# Power_Regulation.net
KiCad netlist of a schematic drawn in Altium Designer
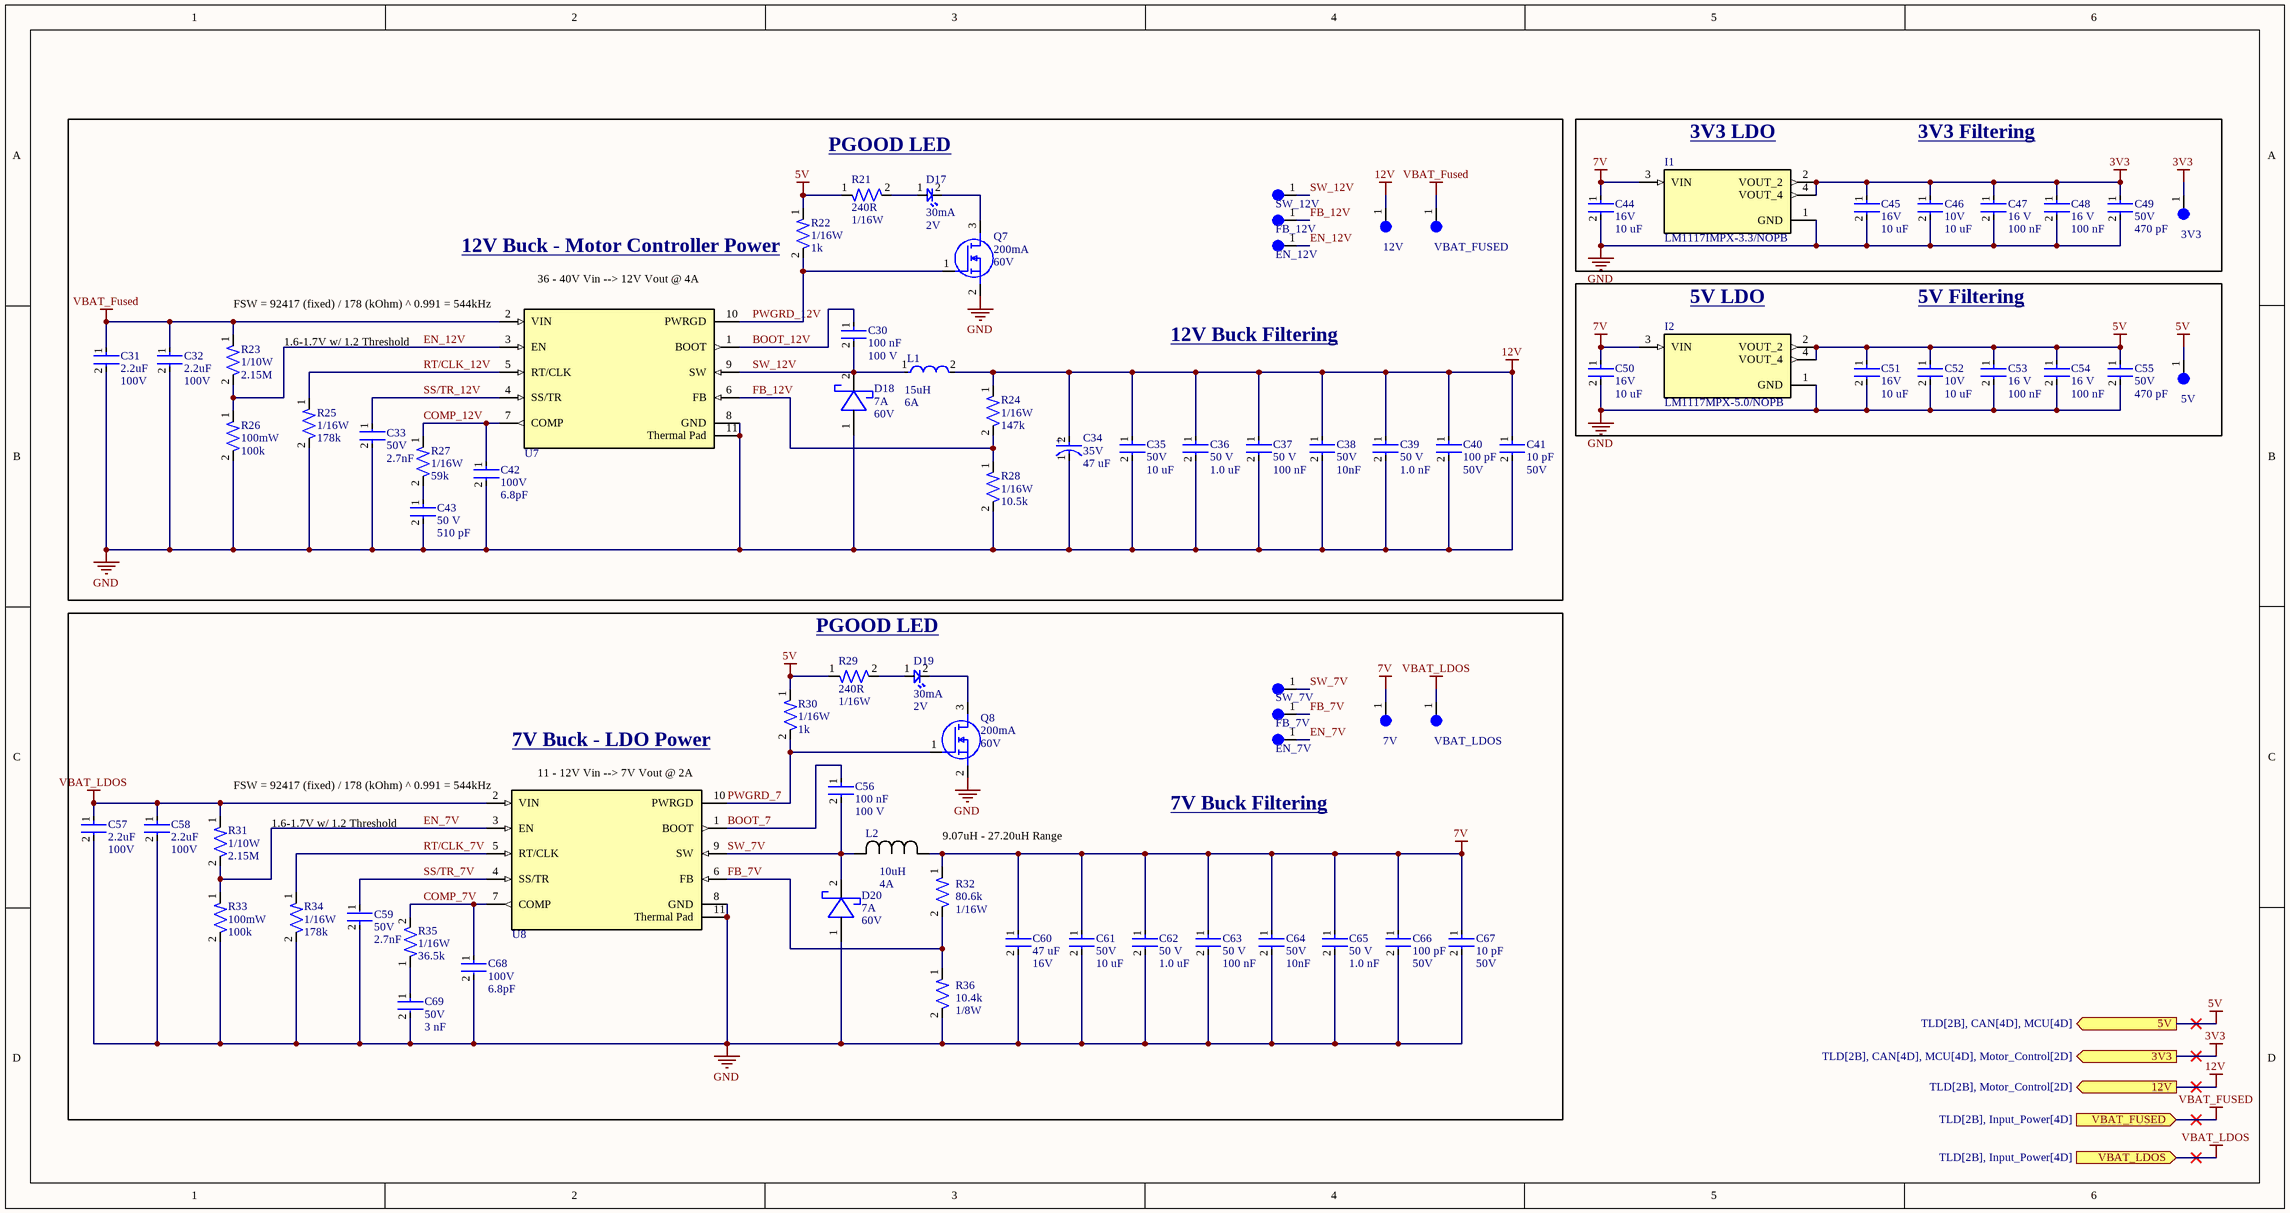
[diagram p0: Power_Regulation.SchDoc]

(export (version "E")
  (design (tool "Eeschema 10.0.6"))
  (components
    (comp (ref "3V3")
      (value "5003")
      (footprint "TEST-POINT-0001")
      (description "Oranange PC Test Point, Miniature Phoisphor Bronze Silver Plating Through Hole Mounting Type")
      (libsource (lib "*") (part "TEST-POINT-0001"))
    )
    (comp (ref "5V")
      (value "5003")
      (footprint "TEST-POINT-0001")
      (description "Oranange PC Test Point, Miniature Phoisphor Bronze Silver Plating Through Hole Mounting Type")
      (libsource (lib "*") (part "TEST-POINT-0001"))
    )
    (comp (ref "7V")
      (value "5003")
      (footprint "TEST-POINT-0001")
      (description "Oranange PC Test Point, Miniature Phoisphor Bronze Silver Plating Through Hole Mounting Type")
      (libsource (lib "*") (part "TEST-POINT-0001"))
    )
    (comp (ref "12V")
      (value "5003")
      (footprint "TEST-POINT-0001")
      (description "Oranange PC Test Point, Miniature Phoisphor Bronze Silver Plating Through Hole Mounting Type")
      (libsource (lib "*") (part "TEST-POINT-0001"))
    )
    (comp (ref "C30")
      (value "CC0603KRX7R0BB104")
      (footprint "CAP-0603")
      (description "CAP CER 0.1UF 100V X7R 0603")
      (fields (field (name "CAPACITANCE") "100 nF") (field (name "VOLTAGE") "100 V"))
      (libsource (lib "JLC_25") (part "CAP-100N-0001"))
    )
    (comp (ref "C31")
      (value "CC1206KKX7R0BB225")
      (footprint "CAP-1206")
      (description "CAP CER 2.2UF 100V X7R 1206")
      (fields (field (name "CAPACITANCE") "2.2uF") (field (name "VOLTAGE") "100V"))
      (libsource (lib "JLC_25") (part "CAP-2.2U-0001"))
    )
    (comp (ref "C32")
      (value "CC1206KKX7R0BB225")
      (footprint "CAP-1206")
      (description "CAP CER 2.2UF 100V X7R 1206")
      (fields (field (name "CAPACITANCE") "2.2uF") (field (name "VOLTAGE") "100V"))
      (libsource (lib "JLC_25") (part "CAP-2.2U-0001"))
    )
    (comp (ref "C33")
      (value "GRM2165C1H272JA01D")
      (footprint "CAP-0805")
      (description "CAP CER 2700PF 50V C0G/NP0 0805")
      (fields (field (name "VOLTAGE") "50V") (field (name "CAPACITANCE") "2.7nF"))
      (libsource (lib "JLC_25") (part "CAP-2.7N-0001"))
    )
    (comp (ref "C34")
      (value "EEH-ZC1V470P")
      (footprint "CAP-Radial-SMD")
      (description "CAP ALUM HYBRID 47UF 20% 35V SMD")
      (fields (field (name "VOLTAGE") "35V") (field (name "CAPACITANCE") "47 uF"))
      (libsource (lib "JLC_25") (part "CAP-47U-0002"))
    )
    (comp (ref "C35")
      (value "CL32B106KBJNNNE")
      (footprint "CAP-1210")
      (description "CAP CER 10UF 50V X7R 1210")
      (fields (field (name "VOLTAGE") "50V") (field (name "CAPACITANCE") "10 uF"))
      (libsource (lib "JLC_25") (part "CAP-10U-0002"))
    )
    (comp (ref "C36")
      (value "CC0805KKX7R9BB105")
      (footprint "CAP-0805")
      (description "CAP CER 1UF 50V X7R 0805")
      (fields (field (name "VOLTAGE") "50 V") (field (name "CAPACITANCE") "1.0 uF"))
      (libsource (lib "JLC_25") (part "CAP-1U-0001"))
    )
    (comp (ref "C37")
      (value "CC0805KRX7R9BB104")
      (footprint "CAP-0805")
      (description "CAP CER 0.1UF 50V X7R 0805")
      (fields (field (name "VOLTAGE RATING") "50 V") (field (name "CAPACITANCE") "100 nF"))
      (libsource (lib "JLC_25") (part "CAP-0.1U-0002"))
    )
    (comp (ref "C38")
      (value "GRM2195C1H103JA01D")
      (footprint "CAP-0805")
      (description "CAP CER 10000PF 50V C0G/NP0 0805")
      (fields (field (name "VOLTAGE") "50V") (field (name "CAPACITANCE") "10nF"))
      (libsource (lib "JLC_25") (part "CAP-10N-0001"))
    )
    (comp (ref "C39")
      (value "CC0402KRX7R9BB102")
      (footprint "CAP-0402")
      (description "CAP CER 1000PF 50V X7R 0402")
      (fields (field (name "VOLTAGE") "50 V") (field (name "CAPACITANCE") "1.0 nF"))
      (libsource (lib "JLC_25") (part "CAP-1N-0001"))
    )
    (comp (ref "C40")
      (value "CC0402JRNPO9BN101")
      (footprint "CAP-0402")
      (description "CAP CER 100PF 50V C0G/NPO 0402")
      (fields (field (name "CAPACITANCE") "100 pF") (field (name "VOLTAGE") "50V"))
      (libsource (lib "JLC_25") (part "CAP-100P-0001"))
    )
    (comp (ref "C41")
      (value "CC0402JRNPO9BN100")
      (footprint "CAP-0402")
      (description "CAP CER 10PF 50V C0G/NPO 0402")
      (fields (field (name "CAPACITANCE") "10 pF") (field (name "VOLTAGE") "50V"))
      (libsource (lib "JLC_25") (part "CAP-10P-0001"))
    )
    (comp (ref "C42")
      (value "CC0603CRNPO0BN6R8")
      (footprint "CAP-0603")
      (description "CAP CER 6.8PF 100V C0G/NPO 0603")
      (fields (field (name "VOLTAGE") "100V") (field (name "CAPACITANCE") "6.8pF"))
      (libsource (lib "JLC_25") (part "CAP-6.8P-0001"))
    )
    (comp (ref "C43")
      (value "0402N511J500CT")
      (footprint "CAP-0402")
      (description "CAP CER 510PF 50V C0G/NP0 0402")
      (fields (field (name "VOLTAGE") "50 V") (field (name "CAPACITANCE") "510 pF"))
      (libsource (lib "JLC_25") (part "CAP-510P-0001"))
    )
    (comp (ref "C44")
      (value "293D106X9016A2TE3")
      (footprint "CAP-1206")
      (description "CAP TANT 10UF 10% 16V 1206")
      (fields (field (name "VOLTAGE") "16V") (field (name "CAPACITANCE") "10 uF"))
      (libsource (lib "JLC_25") (part "CAP-10U-0004"))
    )
    (comp (ref "C45")
      (value "293D106X9016A2TE3")
      (footprint "CAP-1206")
      (description "CAP TANT 10UF 10% 16V 1206")
      (fields (field (name "VOLTAGE") "16V") (field (name "CAPACITANCE") "10 uF"))
      (libsource (lib "JLC_25") (part "CAP-10U-0004"))
    )
    (comp (ref "C46")
      (value "CC0603KRX5R6BB106")
      (footprint "CAP-0603")
      (description "CAP CER 10UF 10V X5R 0603")
      (fields (field (name "VOLTAGE") "10V") (field (name "CAPACITANCE") "10 uF"))
      (libsource (lib "JLC_25") (part "CAP-10U-0001"))
    )
    (comp (ref "C47")
      (value "CC0402KRX7R7BB104")
      (footprint "CAP-0402")
      (description "CAP CER 0.1UF 16V X7R 0402")
      (fields (field (name "VOLTAGE RATING") "16 V") (field (name "CAPACITANCE") "100 nF"))
      (libsource (lib "JLC_25") (part "CAP-0.1U-0001"))
    )
    (comp (ref "C48")
      (value "CC0402KRX7R7BB104")
      (footprint "CAP-0402")
      (description "CAP CER 0.1UF 16V X7R 0402")
      (fields (field (name "VOLTAGE RATING") "16 V") (field (name "CAPACITANCE") "100 nF"))
      (libsource (lib "JLC_25") (part "CAP-0.1U-0001"))
    )
    (comp (ref "C49")
      (value "CC0805JRNPO9BN471")
      (footprint "CAP-0805")
      (description "CAP CER 470PF 50V C0G/NPO 0805")
      (fields (field (name "VOLTAGE") "50V") (field (name "CAPACITANCE") "470 pF"))
      (libsource (lib "JLC_25") (part "CAP-470P-0001"))
    )
    (comp (ref "C50")
      (value "293D106X9016A2TE3")
      (footprint "CAP-1206")
      (description "CAP TANT 10UF 10% 16V 1206")
      (fields (field (name "VOLTAGE") "16V") (field (name "CAPACITANCE") "10 uF"))
      (libsource (lib "JLC_25") (part "CAP-10U-0004"))
    )
    (comp (ref "C51")
      (value "293D106X9016A2TE3")
      (footprint "CAP-1206")
      (description "CAP TANT 10UF 10% 16V 1206")
      (fields (field (name "VOLTAGE") "16V") (field (name "CAPACITANCE") "10 uF"))
      (libsource (lib "JLC_25") (part "CAP-10U-0004"))
    )
    (comp (ref "C52")
      (value "CC0603KRX5R6BB106")
      (footprint "CAP-0603")
      (description "CAP CER 10UF 10V X5R 0603")
      (fields (field (name "VOLTAGE") "10V") (field (name "CAPACITANCE") "10 uF"))
      (libsource (lib "JLC_25") (part "CAP-10U-0001"))
    )
    (comp (ref "C53")
      (value "CC0402KRX7R7BB104")
      (footprint "CAP-0402")
      (description "CAP CER 0.1UF 16V X7R 0402")
      (fields (field (name "VOLTAGE RATING") "16 V") (field (name "CAPACITANCE") "100 nF"))
      (libsource (lib "JLC_25") (part "CAP-0.1U-0001"))
    )
    (comp (ref "C54")
      (value "CC0402KRX7R7BB104")
      (footprint "CAP-0402")
      (description "CAP CER 0.1UF 16V X7R 0402")
      (fields (field (name "VOLTAGE RATING") "16 V") (field (name "CAPACITANCE") "100 nF"))
      (libsource (lib "JLC_25") (part "CAP-0.1U-0001"))
    )
    (comp (ref "C55")
      (value "CC0805JRNPO9BN471")
      (footprint "CAP-0805")
      (description "CAP CER 470PF 50V C0G/NPO 0805")
      (fields (field (name "VOLTAGE") "50V") (field (name "CAPACITANCE") "470 pF"))
      (libsource (lib "JLC_25") (part "CAP-470P-0001"))
    )
    (comp (ref "C56")
      (value "CC0603KRX7R0BB104")
      (footprint "CAP-0603")
      (description "CAP CER 0.1UF 100V X7R 0603")
      (fields (field (name "CAPACITANCE") "100 nF") (field (name "VOLTAGE") "100 V"))
      (libsource (lib "JLC_25") (part "CAP-100N-0001"))
    )
    (comp (ref "C57")
      (value "CC1206KKX7R0BB225")
      (footprint "CAP-1206")
      (description "CAP CER 2.2UF 100V X7R 1206")
      (fields (field (name "CAPACITANCE") "2.2uF") (field (name "VOLTAGE") "100V"))
      (libsource (lib "JLC_25") (part "CAP-2.2U-0001"))
    )
    (comp (ref "C58")
      (value "CC1206KKX7R0BB225")
      (footprint "CAP-1206")
      (description "CAP CER 2.2UF 100V X7R 1206")
      (fields (field (name "CAPACITANCE") "2.2uF") (field (name "VOLTAGE") "100V"))
      (libsource (lib "JLC_25") (part "CAP-2.2U-0001"))
    )
    (comp (ref "C59")
      (value "GRM2165C1H272JA01D")
      (footprint "CAP-0805")
      (description "CAP CER 2700PF 50V C0G/NP0 0805")
      (fields (field (name "VOLTAGE") "50V") (field (name "CAPACITANCE") "2.7nF"))
      (libsource (lib "JLC_25") (part "CAP-2.7N-0001"))
    )
    (comp (ref "C60")
      (value "C3225X7R1N106K250AC")
      (footprint "CAP-1210")
      (description "CAP CER 47UF 16V X5R 1210")
      (fields (field (name "CAPACITANCE") "47 uF") (field (name "VOLTAGE") "16V"))
      (libsource (lib "JLC_25") (part "CAP-47U-0003"))
    )
    (comp (ref "C61")
      (value "CL32B106KBJNNNE")
      (footprint "CAP-1210")
      (description "CAP CER 10UF 50V X7R 1210")
      (fields (field (name "VOLTAGE") "50V") (field (name "CAPACITANCE") "10 uF"))
      (libsource (lib "JLC_25") (part "CAP-10U-0002"))
    )
    (comp (ref "C62")
      (value "CC0805KKX7R9BB105")
      (footprint "CAP-0805")
      (description "CAP CER 1UF 50V X7R 0805")
      (fields (field (name "VOLTAGE") "50 V") (field (name "CAPACITANCE") "1.0 uF"))
      (libsource (lib "JLC_25") (part "CAP-1U-0001"))
    )
    (comp (ref "C63")
      (value "CC0805KRX7R9BB104")
      (footprint "CAP-0805")
      (description "CAP CER 0.1UF 50V X7R 0805")
      (fields (field (name "VOLTAGE RATING") "50 V") (field (name "CAPACITANCE") "100 nF"))
      (libsource (lib "JLC_25") (part "CAP-0.1U-0002"))
    )
    (comp (ref "C64")
      (value "GRM2195C1H103JA01D")
      (footprint "CAP-0805")
      (description "CAP CER 10000PF 50V C0G/NP0 0805")
      (fields (field (name "VOLTAGE") "50V") (field (name "CAPACITANCE") "10nF"))
      (libsource (lib "JLC_25") (part "CAP-10N-0001"))
    )
    (comp (ref "C65")
      (value "CC0402KRX7R9BB102")
      (footprint "CAP-0402")
      (description "CAP CER 1000PF 50V X7R 0402")
      (fields (field (name "VOLTAGE") "50 V") (field (name "CAPACITANCE") "1.0 nF"))
      (libsource (lib "JLC_25") (part "CAP-1N-0001"))
    )
    (comp (ref "C66")
      (value "CC0402JRNPO9BN101")
      (footprint "CAP-0402")
      (description "CAP CER 100PF 50V C0G/NPO 0402")
      (fields (field (name "CAPACITANCE") "100 pF") (field (name "VOLTAGE") "50V"))
      (libsource (lib "JLC_25") (part "CAP-100P-0001"))
    )
    (comp (ref "C67")
      (value "CC0402JRNPO9BN100")
      (footprint "CAP-0402")
      (description "CAP CER 10PF 50V C0G/NPO 0402")
      (fields (field (name "CAPACITANCE") "10 pF") (field (name "VOLTAGE") "50V"))
      (libsource (lib "JLC_25") (part "CAP-10P-0001"))
    )
    (comp (ref "C68")
      (value "CC0603CRNPO0BN6R8")
      (footprint "CAP-0603")
      (description "CAP CER 6.8PF 100V C0G/NPO 0603")
      (fields (field (name "VOLTAGE") "100V") (field (name "CAPACITANCE") "6.8pF"))
      (libsource (lib "JLC_25") (part "CAP-6.8P-0001"))
    )
    (comp (ref "C69")
      (value "GRM1885C1H302JA01D")
      (footprint "CAP-0603")
      (description "3000 pF ±5% 50V Ceramic Capacitor C0G, NP0 0603 (1608 Metric)")
      (fields (field (name "VOLTAGE") "50V") (field (name "CAPACITANCE") "3 nF"))
      (libsource (lib "JLC_25") (part "CAP-3N-0001"))
    )
    (comp (ref "D17")
      (value "BL-HKC36G-AV-TRB")
      (footprint "LED-0603")
      (description "LED YELLOW CLEAR 0603 SMD")
      (fields (field (name "FORWARD CURRENT") "30mA") (field (name "FORWARD VOLTAGE") "2V"))
      (libsource (lib "JLC_25") (part "LED-0001"))
    )
    (comp (ref "D18")
      (value "PDS760-13")
      (footprint "DO-POWERDI5")
      (description "DIODE SCHOTTKY 60V 7A POWERDI5")
      (fields (field (name "FORWARD CURRENT") "7A") (field (name "REVERSE VOLTAGE (DC)") "60V"))
      (libsource (lib "JLC_25") (part "DIO-SCHOTTKY-0001"))
    )
    (comp (ref "D19")
      (value "BL-HKC36G-AV-TRB")
      (footprint "LED-0603")
      (description "LED YELLOW CLEAR 0603 SMD")
      (fields (field (name "FORWARD CURRENT") "30mA") (field (name "FORWARD VOLTAGE") "2V"))
      (libsource (lib "JLC_25") (part "LED-0001"))
    )
    (comp (ref "D20")
      (value "PDS760-13")
      (footprint "DO-POWERDI5")
      (description "DIODE SCHOTTKY 60V 7A POWERDI5")
      (fields (field (name "FORWARD CURRENT") "7A") (field (name "REVERSE VOLTAGE (DC)") "60V"))
      (libsource (lib "JLC_25") (part "DIO-SCHOTTKY-0001"))
    )
    (comp (ref "EN_7V")
      (value "5003")
      (footprint "TEST-POINT-0001")
      (description "Oranange PC Test Point, Miniature Phoisphor Bronze Silver Plating Through Hole Mounting Type")
      (libsource (lib "*") (part "TEST-POINT-0001"))
    )
    (comp (ref "EN_12V")
      (value "5003")
      (footprint "TEST-POINT-0001")
      (description "Oranange PC Test Point, Miniature Phoisphor Bronze Silver Plating Through Hole Mounting Type")
      (libsource (lib "*") (part "TEST-POINT-0001"))
    )
    (comp (ref "FB_7V")
      (value "5003")
      (footprint "TEST-POINT-0001")
      (description "Oranange PC Test Point, Miniature Phoisphor Bronze Silver Plating Through Hole Mounting Type")
      (libsource (lib "*") (part "TEST-POINT-0001"))
    )
    (comp (ref "FB_12V")
      (value "5003")
      (footprint "TEST-POINT-0001")
      (description "Oranange PC Test Point, Miniature Phoisphor Bronze Silver Plating Through Hole Mounting Type")
      (libsource (lib "*") (part "TEST-POINT-0001"))
    )
    (comp (ref "I1")
      (value "LM1117IMPX-3.3/NOPB")
      (footprint "IC-SOT-223-4")
      (description "IC REG LIN 3.3V 800MA SOT223-4")
      (libsource (lib "JLC_25") (part "IC_LDO_3V3_0001"))
    )
    (comp (ref "I2")
      (value "LM1117MPX-5.0/NOPB")
      (footprint "IC-SOT-223-4")
      (description "IC REG LINEAR 5V 800MA SOT223-4")
      (libsource (lib "JLC_25") (part "IC_LDO_5V_0001"))
    )
    (comp (ref "L1")
      (value "CSAD1010-150M")
      (footprint "IND-15U-0002")
      (description "SMD MOLDING POWER CHOKE")
      (fields (field (name "INDUCTANCE") "15uH") (field (name "CURRENT RATING") "6A"))
      (libsource (lib "JLC_25") (part "IND-15U-0002-NoJLC"))
    )
    (comp (ref "L2")
      (value "IHLP2525CZER100M11")
      (footprint "IND_IHLP_2525_CZ_VIS")
      (description "IHLP-2525CZ-11 10 20% ER E3")
      (fields
        (field (name "CURRENT") "4A")
        (field (name "INDUCTANCE") "10uH")
        (field (name "COPYRIGHT") "Copyright (C) 2025 Ultra Librarian. All rights reserved.")
      )
      (libsource (lib "JLC_25") (part "IND-10U-0002"))
    )
    (comp (ref "Q7")
      (value "T2N7002AK,LM")
      (footprint "IC-SOT23-3")
      (description "MOSFET N-CH 60V 200MA SOT23")
      (fields (field (name "CONTINUOUS CURRENT") "200mA") (field (name "VOLTAGE") "60V"))
      (libsource (lib "JLC_25") (part "NMOS-200MA-0001"))
    )
    (comp (ref "Q8")
      (value "T2N7002AK,LM")
      (footprint "IC-SOT23-3")
      (description "MOSFET N-CH 60V 200MA SOT23")
      (fields (field (name "CONTINUOUS CURRENT") "200mA") (field (name "VOLTAGE") "60V"))
      (libsource (lib "JLC_25") (part "NMOS-200MA-0001"))
    )
    (comp (ref "R21")
      (value "RC0402FR-07240RL")
      (footprint "RES-0402")
      (description "240R 0.063W 1% 0402 (1005 Metric)  SMD")
      (fields
        (field (name "TOLERANCE") "1%")
        (field (name "RESISTANCE") "240R")
        (field (name "POWER") "1/16W")
      )
      (libsource (lib "JLC_25") (part "RES-240-0001"))
    )
    (comp (ref "R22")
      (value "RC0402FR-071KL")
      (footprint "RES-0402")
      (description "RES 1K OHM 1% 1/16W 0402")
      (fields (field (name "TOLERANCE") "1%") (field (name "POWER") "1/16W") (field (name "RESISTANCE") "1k"))
      (libsource (lib "JLC_25") (part "RES-1k-0001"))
    )
    (comp (ref "R23")
      (value "RC0603FR-072M15L")
      (footprint "RES-0603")
      (description "RES SMD 2.15M OHM 1% 1/10W 0603")
      (fields
        (field (name "TOLERANCE") "1%")
        (field (name "POWER") "1/10W")
        (field (name "RESISTANCE") "2.15M")
      )
      (libsource (lib "JLC_25") (part "RES-2.15M-0001"))
    )
    (comp (ref "R24")
      (value "RC0402FR-07147KL")
      (footprint "RES-0402")
      (description "RES 147K OHM 1% 1/16W 0402")
      (fields
        (field (name "TOLERANCE") "1%")
        (field (name "POWER") "1/16W")
        (field (name "RESISTANCE") "147k")
      )
      (libsource (lib "JLC_25") (part "RES-147k-0001"))
    )
    (comp (ref "R25")
      (value "RTT021783FTH")
      (footprint "RES-0402")
      (description "62.5mW Thick Film Resistors 50V ±100ppm/℃ ±1% 178kΩ 0402 Chip Resistor - Surface Mount ROHS")
      (fields
        (field (name "TOLERANCE") "1%")
        (field (name "POWER") "1/16W")
        (field (name "RESISTANCE") "178k")
      )
      (libsource (lib "JLC_25") (part "RES-178k-0001"))
    )
    (comp (ref "R26")
      (value "RC0603FR-07100KL")
      (footprint "RES-0603")
      (description "RES SMD 100K OHM 1% 1/10W 0603")
      (fields
        (field (name "TOLERANCE") "1%")
        (field (name "POWER") "100mW")
        (field (name "RESISTANCE") "100k")
      )
      (libsource (lib "JLC_25") (part "RES-100k-0001"))
    )
    (comp (ref "R27")
      (value "RC0402FR-0759KL")
      (footprint "RES-0402")
      (description "RES 59K OHM 1% 1/16W 0402")
      (fields
        (field (name "TOLERANCE") "1%")
        (field (name "POWER") "1/16W")
        (field (name "RESISTANCE") "59k")
      )
      (libsource (lib "JLC_25") (part "RES-59k-0001"))
    )
    (comp (ref "R28")
      (value "RC0402FR-0710K5L")
      (footprint "RES-0402")
      (description "RES 10.5K OHM 1% 1/16W 0402")
      (fields
        (field (name "TOLERANCE") "1%")
        (field (name "POWER") "1/16W")
        (field (name "RESISTANCE") "10.5k")
      )
      (libsource (lib "JLC_25") (part "RES-10.5k-0001"))
    )
    (comp (ref "R29")
      (value "RC0402FR-07240RL")
      (footprint "RES-0402")
      (description "240R 0.063W 1% 0402 (1005 Metric)  SMD")
      (fields
        (field (name "TOLERANCE") "1%")
        (field (name "RESISTANCE") "240R")
        (field (name "POWER") "1/16W")
      )
      (libsource (lib "JLC_25") (part "RES-240-0001"))
    )
    (comp (ref "R30")
      (value "RC0402FR-071KL")
      (footprint "RES-0402")
      (description "RES 1K OHM 1% 1/16W 0402")
      (fields (field (name "TOLERANCE") "1%") (field (name "POWER") "1/16W") (field (name "RESISTANCE") "1k"))
      (libsource (lib "JLC_25") (part "RES-1k-0001"))
    )
    (comp (ref "R31")
      (value "RC0603FR-072M15L")
      (footprint "RES-0603")
      (description "RES SMD 2.15M OHM 1% 1/10W 0603")
      (fields
        (field (name "TOLERANCE") "1%")
        (field (name "POWER") "1/10W")
        (field (name "RESISTANCE") "2.15M")
      )
      (libsource (lib "JLC_25") (part "RES-2.15M-0001"))
    )
    (comp (ref "R32")
      (value "RC0402FR-0780K6L")
      (footprint "RES-0402")
      (description "80.6 kOhms ±1% 0.063W, 1/16W Chip Resistor 0402 (1005 Metric) Moisture Resistant Thick Film")
      (fields
        (field (name "TOLERANCE") "1%")
        (field (name "RESISTANCE") "80.6k")
        (field (name "POWER") "1/16W")
      )
      (libsource (lib "JLC_25") (part "RES-80.6k-0001"))
    )
    (comp (ref "R33")
      (value "RC0603FR-07100KL")
      (footprint "RES-0603")
      (description "RES SMD 100K OHM 1% 1/10W 0603")
      (fields
        (field (name "TOLERANCE") "1%")
        (field (name "POWER") "100mW")
        (field (name "RESISTANCE") "100k")
      )
      (libsource (lib "JLC_25") (part "RES-100k-0001"))
    )
    (comp (ref "R34")
      (value "RTT021783FTH")
      (footprint "RES-0402")
      (description "62.5mW Thick Film Resistors 50V ±100ppm/℃ ±1% 178kΩ 0402 Chip Resistor - Surface Mount ROHS")
      (fields
        (field (name "TOLERANCE") "1%")
        (field (name "POWER") "1/16W")
        (field (name "RESISTANCE") "178k")
      )
      (libsource (lib "JLC_25") (part "RES-178k-0001"))
    )
    (comp (ref "R35")
      (value "RC0402FR-0736K5L")
      (footprint "RES-0402")
      (description "36.5 kOhms ±1% 0.063W, 1/16W Chip Resistor 0402 (1005 Metric) Moisture Resistant Thick Film")
      (fields (field (name "POWER") "1/16W") (field (name "RESISTANCE") "36.5k"))
      (libsource (lib "JLC_25") (part "RES-36.5k-0001"))
    )
    (comp (ref "R36")
      (value "RT0805BRD0710K4L")
      (footprint "RES-0805")
      (description "10.4 kOhms ±0.1% 0.125W, 1/8W Chip Resistor 0805 (2012 Metric) Thin Film")
      (fields
        (field (name "TOLERANCE") "1%")
        (field (name "POWER") "1/8W")
        (field (name "RESISTANCE") "10.4k")
      )
      (libsource (lib "JLC_25") (part "RES-10.4k-0001"))
    )
    (comp (ref "SW_7V")
      (value "5003")
      (footprint "TEST-POINT-0001")
      (description "Oranange PC Test Point, Miniature Phoisphor Bronze Silver Plating Through Hole Mounting Type")
      (libsource (lib "*") (part "TEST-POINT-0001"))
    )
    (comp (ref "SW_12V")
      (value "5003")
      (footprint "TEST-POINT-0001")
      (description "Oranange PC Test Point, Miniature Phoisphor Bronze Silver Plating Through Hole Mounting Type")
      (libsource (lib "*") (part "TEST-POINT-0001"))
    )
    (comp (ref "U7")
      (value "TPS54561DPRR")
      (footprint "IC-10WSON")
      (description "IC REG BUCK ADJ 5A 10WSON")
      (libsource (lib "JLC_25") (part "IC-BUCK-0001"))
    )
    (comp (ref "U8")
      (value "TPS54561DPRR")
      (footprint "IC-10WSON")
      (description "IC REG BUCK ADJ 5A 10WSON")
      (libsource (lib "JLC_25") (part "IC-BUCK-0001"))
    )
    (comp (ref "VBAT_FUSED")
      (value "5003")
      (footprint "TEST-POINT-0001")
      (description "Oranange PC Test Point, Miniature Phoisphor Bronze Silver Plating Through Hole Mounting Type")
      (libsource (lib "*") (part "TEST-POINT-0001"))
    )
    (comp (ref "VBAT_LDOS")
      (value "5003")
      (footprint "TEST-POINT-0001")
      (description "Oranange PC Test Point, Miniature Phoisphor Bronze Silver Plating Through Hole Mounting Type")
      (libsource (lib "*") (part "TEST-POINT-0001"))
    )
  )
  (nets
    (net (code "1") (name "/BOOT_7") (class "Default")
      (node (ref "C56") (pin "1") (pinfunction "1_1") (pintype "passive"))
      (node (ref "U8") (pin "1") (pinfunction "BOOT_1") (pintype "output"))
    )
    (net (code "2") (name "/BOOT_12V") (class "Default")
      (node (ref "C30") (pin "1") (pinfunction "1_1") (pintype "passive"))
      (node (ref "U7") (pin "1") (pinfunction "BOOT_1") (pintype "output"))
    )
    (net (code "3") (name "/COMP_7V") (class "Default")
      (node (ref "C68") (pin "1") (pinfunction "1_1") (pintype "passive"))
      (node (ref "R35") (pin "2") (pinfunction "2_2") (pintype "passive"))
      (node (ref "U8") (pin "7") (pinfunction "COMP_7") (pintype "output"))
    )
    (net (code "4") (name "/COMP_12V") (class "Default")
      (node (ref "C42") (pin "1") (pinfunction "1_1") (pintype "passive"))
      (node (ref "R27") (pin "1") (pinfunction "1_1") (pintype "passive"))
      (node (ref "U7") (pin "7") (pinfunction "COMP_7") (pintype "output"))
    )
    (net (code "5") (name "/EN_7V") (class "Default")
      (node (ref "EN_7V") (pin "1") (pinfunction "0_1") (pintype "passive"))
      (node (ref "R31") (pin "2") (pinfunction "2_2") (pintype "passive"))
      (node (ref "R33") (pin "1") (pinfunction "1_1") (pintype "passive"))
      (node (ref "U8") (pin "3") (pinfunction "EN_3") (pintype "input"))
    )
    (net (code "6") (name "/EN_12V") (class "Default")
      (node (ref "EN_12V") (pin "1") (pinfunction "0_1") (pintype "passive"))
      (node (ref "R23") (pin "2") (pinfunction "2_2") (pintype "passive"))
      (node (ref "R26") (pin "1") (pinfunction "1_1") (pintype "passive"))
      (node (ref "U7") (pin "3") (pinfunction "EN_3") (pintype "input"))
    )
    (net (code "7") (name "/FB_7V") (class "Default")
      (node (ref "FB_7V") (pin "1") (pinfunction "0_1") (pintype "passive"))
      (node (ref "R32") (pin "2") (pinfunction "2_2") (pintype "passive"))
      (node (ref "R36") (pin "1") (pinfunction "1_1") (pintype "passive"))
      (node (ref "U8") (pin "6") (pinfunction "FB_6") (pintype "input"))
    )
    (net (code "8") (name "/FB_12V") (class "Default")
      (node (ref "FB_12V") (pin "1") (pinfunction "0_1") (pintype "passive"))
      (node (ref "R24") (pin "2") (pinfunction "2_2") (pintype "passive"))
      (node (ref "R28") (pin "1") (pinfunction "1_1") (pintype "passive"))
      (node (ref "U7") (pin "6") (pinfunction "FB_6") (pintype "input"))
    )
    (net (code "9") (name "/PWGRD_7") (class "Default")
      (node (ref "Q8") (pin "1") (pinfunction "G_1") (pintype "passive"))
      (node (ref "R30") (pin "2") (pinfunction "2_2") (pintype "passive"))
      (node (ref "U8") (pin "10") (pinfunction "PWRGD_10") (pintype "open_collector"))
    )
    (net (code "10") (name "/PWGRD_12V") (class "Default")
      (node (ref "Q7") (pin "1") (pinfunction "G_1") (pintype "passive"))
      (node (ref "R22") (pin "2") (pinfunction "2_2") (pintype "passive"))
      (node (ref "U7") (pin "10") (pinfunction "PWRGD_10") (pintype "open_collector"))
    )
    (net (code "11") (name "/RT{slash}CLK_7V") (class "Default")
      (node (ref "R34") (pin "1") (pinfunction "1_1") (pintype "passive"))
      (node (ref "U8") (pin "5") (pinfunction "RT/CLK_5") (pintype "input"))
    )
    (net (code "12") (name "/RT{slash}CLK_12V") (class "Default")
      (node (ref "R25") (pin "1") (pinfunction "1_1") (pintype "passive"))
      (node (ref "U7") (pin "5") (pinfunction "RT/CLK_5") (pintype "input"))
    )
    (net (code "13") (name "/SS{slash}TR_7V") (class "Default")
      (node (ref "C59") (pin "1") (pinfunction "1_1") (pintype "passive"))
      (node (ref "U8") (pin "4") (pinfunction "SS/TR_4") (pintype "input"))
    )
    (net (code "14") (name "/SS{slash}TR_12V") (class "Default")
      (node (ref "C33") (pin "1") (pinfunction "1_1") (pintype "passive"))
      (node (ref "U7") (pin "4") (pinfunction "SS/TR_4") (pintype "input"))
    )
    (net (code "15") (name "/SW_7V") (class "Default")
      (node (ref "C56") (pin "2") (pinfunction "2_2") (pintype "passive"))
      (node (ref "D20") (pin "2") (pinfunction "ANODE_2") (pintype "passive"))
      (node (ref "L2") (pin "2") (pinfunction "2_2") (pintype "passive"))
      (node (ref "SW_7V") (pin "1") (pinfunction "0_1") (pintype "passive"))
      (node (ref "U8") (pin "9") (pinfunction "SW_9") (pintype "input"))
    )
    (net (code "16") (name "/SW_12V") (class "Default")
      (node (ref "C30") (pin "2") (pinfunction "2_2") (pintype "passive"))
      (node (ref "D18") (pin "2") (pinfunction "ANODE_2") (pintype "passive"))
      (node (ref "L1") (pin "1") (pinfunction "1_1") (pintype "passive"))
      (node (ref "SW_12V") (pin "1") (pinfunction "0_1") (pintype "passive"))
      (node (ref "U7") (pin "9") (pinfunction "SW_9") (pintype "input"))
    )
    (net (code "17") (name "3V3") (class "Default")
      (node (ref "3V3") (pin "1") (pinfunction "0_1") (pintype "passive"))
      (node (ref "C45") (pin "1") (pinfunction "1_1") (pintype "passive"))
      (node (ref "C46") (pin "1") (pinfunction "1_1") (pintype "passive"))
      (node (ref "C47") (pin "1") (pinfunction "1_1") (pintype "passive"))
      (node (ref "C48") (pin "1") (pinfunction "1_1") (pintype "passive"))
      (node (ref "C49") (pin "1") (pinfunction "1_1") (pintype "passive"))
      (node (ref "I1") (pin "2") (pinfunction "VOUT_2_2") (pintype "output"))
      (node (ref "I1") (pin "4") (pinfunction "VOUT_4_4") (pintype "output"))
    )
    (net (code "18") (name "5V") (class "Default")
      (node (ref "5V") (pin "1") (pinfunction "0_1") (pintype "passive"))
      (node (ref "C51") (pin "1") (pinfunction "1_1") (pintype "passive"))
      (node (ref "C52") (pin "1") (pinfunction "1_1") (pintype "passive"))
      (node (ref "C53") (pin "1") (pinfunction "1_1") (pintype "passive"))
      (node (ref "C54") (pin "1") (pinfunction "1_1") (pintype "passive"))
      (node (ref "C55") (pin "1") (pinfunction "1_1") (pintype "passive"))
      (node (ref "I2") (pin "2") (pinfunction "VOUT_2_2") (pintype "output"))
      (node (ref "I2") (pin "4") (pinfunction "VOUT_4_4") (pintype "output"))
      (node (ref "R21") (pin "1") (pinfunction "1_1") (pintype "passive"))
      (node (ref "R22") (pin "1") (pinfunction "1_1") (pintype "passive"))
      (node (ref "R29") (pin "1") (pinfunction "1_1") (pintype "passive"))
      (node (ref "R30") (pin "1") (pinfunction "1_1") (pintype "passive"))
    )
    (net (code "19") (name "7V") (class "Default")
      (node (ref "7V") (pin "1") (pinfunction "0_1") (pintype "passive"))
      (node (ref "C44") (pin "1") (pinfunction "1_1") (pintype "passive"))
      (node (ref "C50") (pin "1") (pinfunction "1_1") (pintype "passive"))
      (node (ref "C60") (pin "1") (pinfunction "1_1") (pintype "passive"))
      (node (ref "C61") (pin "1") (pinfunction "1_1") (pintype "passive"))
      (node (ref "C62") (pin "1") (pinfunction "1_1") (pintype "passive"))
      (node (ref "C63") (pin "1") (pinfunction "1_1") (pintype "passive"))
      (node (ref "C64") (pin "1") (pinfunction "1_1") (pintype "passive"))
      (node (ref "C65") (pin "1") (pinfunction "1_1") (pintype "passive"))
      (node (ref "C66") (pin "1") (pinfunction "1_1") (pintype "passive"))
      (node (ref "C67") (pin "1") (pinfunction "1_1") (pintype "passive"))
      (node (ref "I1") (pin "3") (pinfunction "VIN_3") (pintype "input"))
      (node (ref "I2") (pin "3") (pinfunction "VIN_3") (pintype "input"))
      (node (ref "L2") (pin "1") (pinfunction "1_1") (pintype "passive"))
      (node (ref "R32") (pin "1") (pinfunction "1_1") (pintype "passive"))
    )
    (net (code "20") (name "12V") (class "Default")
      (node (ref "12V") (pin "1") (pinfunction "0_1") (pintype "passive"))
      (node (ref "C34") (pin "2") (pinfunction "A_2") (pintype "passive"))
      (node (ref "C35") (pin "1") (pinfunction "1_1") (pintype "passive"))
      (node (ref "C36") (pin "1") (pinfunction "1_1") (pintype "passive"))
      (node (ref "C37") (pin "1") (pinfunction "1_1") (pintype "passive"))
      (node (ref "C38") (pin "1") (pinfunction "1_1") (pintype "passive"))
      (node (ref "C39") (pin "1") (pinfunction "1_1") (pintype "passive"))
      (node (ref "C40") (pin "1") (pinfunction "1_1") (pintype "passive"))
      (node (ref "C41") (pin "1") (pinfunction "1_1") (pintype "passive"))
      (node (ref "L1") (pin "2") (pinfunction "2_2") (pintype "passive"))
      (node (ref "R24") (pin "1") (pinfunction "1_1") (pintype "passive"))
    )
    (net (code "21") (name "GND") (class "Default")
      (node (ref "C31") (pin "2") (pinfunction "2_2") (pintype "passive"))
      (node (ref "C32") (pin "2") (pinfunction "2_2") (pintype "passive"))
      (node (ref "C33") (pin "2") (pinfunction "2_2") (pintype "passive"))
      (node (ref "C34") (pin "1") (pinfunction "C_1") (pintype "passive"))
      (node (ref "C35") (pin "2") (pinfunction "2_2") (pintype "passive"))
      (node (ref "C36") (pin "2") (pinfunction "2_2") (pintype "passive"))
      (node (ref "C37") (pin "2") (pinfunction "2_2") (pintype "passive"))
      (node (ref "C38") (pin "2") (pinfunction "2_2") (pintype "passive"))
      (node (ref "C39") (pin "2") (pinfunction "2_2") (pintype "passive"))
      (node (ref "C40") (pin "2") (pinfunction "2_2") (pintype "passive"))
      (node (ref "C41") (pin "2") (pinfunction "2_2") (pintype "passive"))
      (node (ref "C42") (pin "2") (pinfunction "2_2") (pintype "passive"))
      (node (ref "C43") (pin "2") (pinfunction "2_2") (pintype "passive"))
      (node (ref "C44") (pin "2") (pinfunction "2_2") (pintype "passive"))
      (node (ref "C45") (pin "2") (pinfunction "2_2") (pintype "passive"))
      (node (ref "C46") (pin "2") (pinfunction "2_2") (pintype "passive"))
      (node (ref "C47") (pin "2") (pinfunction "2_2") (pintype "passive"))
      (node (ref "C48") (pin "2") (pinfunction "2_2") (pintype "passive"))
      (node (ref "C49") (pin "2") (pinfunction "2_2") (pintype "passive"))
      (node (ref "C50") (pin "2") (pinfunction "2_2") (pintype "passive"))
      (node (ref "C51") (pin "2") (pinfunction "2_2") (pintype "passive"))
      (node (ref "C52") (pin "2") (pinfunction "2_2") (pintype "passive"))
      (node (ref "C53") (pin "2") (pinfunction "2_2") (pintype "passive"))
      (node (ref "C54") (pin "2") (pinfunction "2_2") (pintype "passive"))
      (node (ref "C55") (pin "2") (pinfunction "2_2") (pintype "passive"))
      (node (ref "C57") (pin "2") (pinfunction "2_2") (pintype "passive"))
      (node (ref "C58") (pin "2") (pinfunction "2_2") (pintype "passive"))
      (node (ref "C59") (pin "2") (pinfunction "2_2") (pintype "passive"))
      (node (ref "C60") (pin "2") (pinfunction "2_2") (pintype "passive"))
      (node (ref "C61") (pin "2") (pinfunction "2_2") (pintype "passive"))
      (node (ref "C62") (pin "2") (pinfunction "2_2") (pintype "passive"))
      (node (ref "C63") (pin "2") (pinfunction "2_2") (pintype "passive"))
      (node (ref "C64") (pin "2") (pinfunction "2_2") (pintype "passive"))
      (node (ref "C65") (pin "2") (pinfunction "2_2") (pintype "passive"))
      (node (ref "C66") (pin "2") (pinfunction "2_2") (pintype "passive"))
      (node (ref "C67") (pin "2") (pinfunction "2_2") (pintype "passive"))
      (node (ref "C68") (pin "2") (pinfunction "2_2") (pintype "passive"))
      (node (ref "C69") (pin "2") (pinfunction "2_2") (pintype "passive"))
      (node (ref "D18") (pin "1") (pinfunction "CATHODE_1") (pintype "passive"))
      (node (ref "D20") (pin "1") (pinfunction "CATHODE_1") (pintype "passive"))
      (node (ref "I1") (pin "1") (pinfunction "GND_1") (pintype "power_in"))
      (node (ref "I2") (pin "1") (pinfunction "GND_1") (pintype "power_in"))
      (node (ref "Q7") (pin "2") (pinfunction "S_2") (pintype "passive"))
      (node (ref "Q8") (pin "2") (pinfunction "S_2") (pintype "passive"))
      (node (ref "R25") (pin "2") (pinfunction "2_2") (pintype "passive"))
      (node (ref "R26") (pin "2") (pinfunction "2_2") (pintype "passive"))
      (node (ref "R28") (pin "2") (pinfunction "2_2") (pintype "passive"))
      (node (ref "R33") (pin "2") (pinfunction "2_2") (pintype "passive"))
      (node (ref "R34") (pin "2") (pinfunction "2_2") (pintype "passive"))
      (node (ref "R36") (pin "2") (pinfunction "2_2") (pintype "passive"))
      (node (ref "U7") (pin "11") (pinfunction "Thermal_Pad_11") (pintype "power_in"))
      (node (ref "U7") (pin "8") (pinfunction "GND_8") (pintype "power_in"))
      (node (ref "U8") (pin "11") (pinfunction "Thermal_Pad_11") (pintype "power_in"))
      (node (ref "U8") (pin "8") (pinfunction "GND_8") (pintype "power_in"))
    )
    (net (code "22") (name "Net-(C43-Pad1)") (class "Default")
      (node (ref "C43") (pin "1") (pinfunction "1_1") (pintype "passive"))
      (node (ref "R27") (pin "2") (pinfunction "2_2") (pintype "passive"))
    )
    (net (code "23") (name "Net-(C69-Pad1)") (class "Default")
      (node (ref "C69") (pin "1") (pinfunction "1_1") (pintype "passive"))
      (node (ref "R35") (pin "1") (pinfunction "1_1") (pintype "passive"))
    )
    (net (code "24") (name "Net-(D17-Pad1)") (class "Default")
      (node (ref "D17") (pin "1") (pinfunction "1_1") (pintype "passive"))
      (node (ref "R21") (pin "2") (pinfunction "2_2") (pintype "passive"))
    )
    (net (code "25") (name "Net-(D19-Pad1)") (class "Default")
      (node (ref "D19") (pin "1") (pinfunction "1_1") (pintype "passive"))
      (node (ref "R29") (pin "2") (pinfunction "2_2") (pintype "passive"))
    )
    (net (code "26") (name "Net-(Q7-D)") (class "Default")
      (node (ref "D17") (pin "2") (pinfunction "2_2") (pintype "passive"))
      (node (ref "Q7") (pin "3") (pinfunction "D_3") (pintype "passive"))
    )
    (net (code "27") (name "Net-(Q8-D)") (class "Default")
      (node (ref "D19") (pin "2") (pinfunction "2_2") (pintype "passive"))
      (node (ref "Q8") (pin "3") (pinfunction "D_3") (pintype "passive"))
    )
    (net (code "29") (name "VBAT_Fused") (class "Default")
      (node (ref "C31") (pin "1") (pinfunction "1_1") (pintype "passive"))
      (node (ref "C32") (pin "1") (pinfunction "1_1") (pintype "passive"))
      (node (ref "R23") (pin "1") (pinfunction "1_1") (pintype "passive"))
      (node (ref "U7") (pin "2") (pinfunction "VIN_2") (pintype "input"))
      (node (ref "VBAT_FUSED") (pin "1") (pinfunction "0_1") (pintype "passive"))
    )
    (net (code "30") (name "VBAT_LDOS") (class "Default")
      (node (ref "C57") (pin "1") (pinfunction "1_1") (pintype "passive"))
      (node (ref "C58") (pin "1") (pinfunction "1_1") (pintype "passive"))
      (node (ref "R31") (pin "1") (pinfunction "1_1") (pintype "passive"))
      (node (ref "U8") (pin "2") (pinfunction "VIN_2") (pintype "input"))
      (node (ref "VBAT_LDOS") (pin "1") (pinfunction "0_1") (pintype "passive"))
    )
  )
)
